# ActiveDebugger8p1.net
KiCad netlist of a schematic drawn in EAGLE
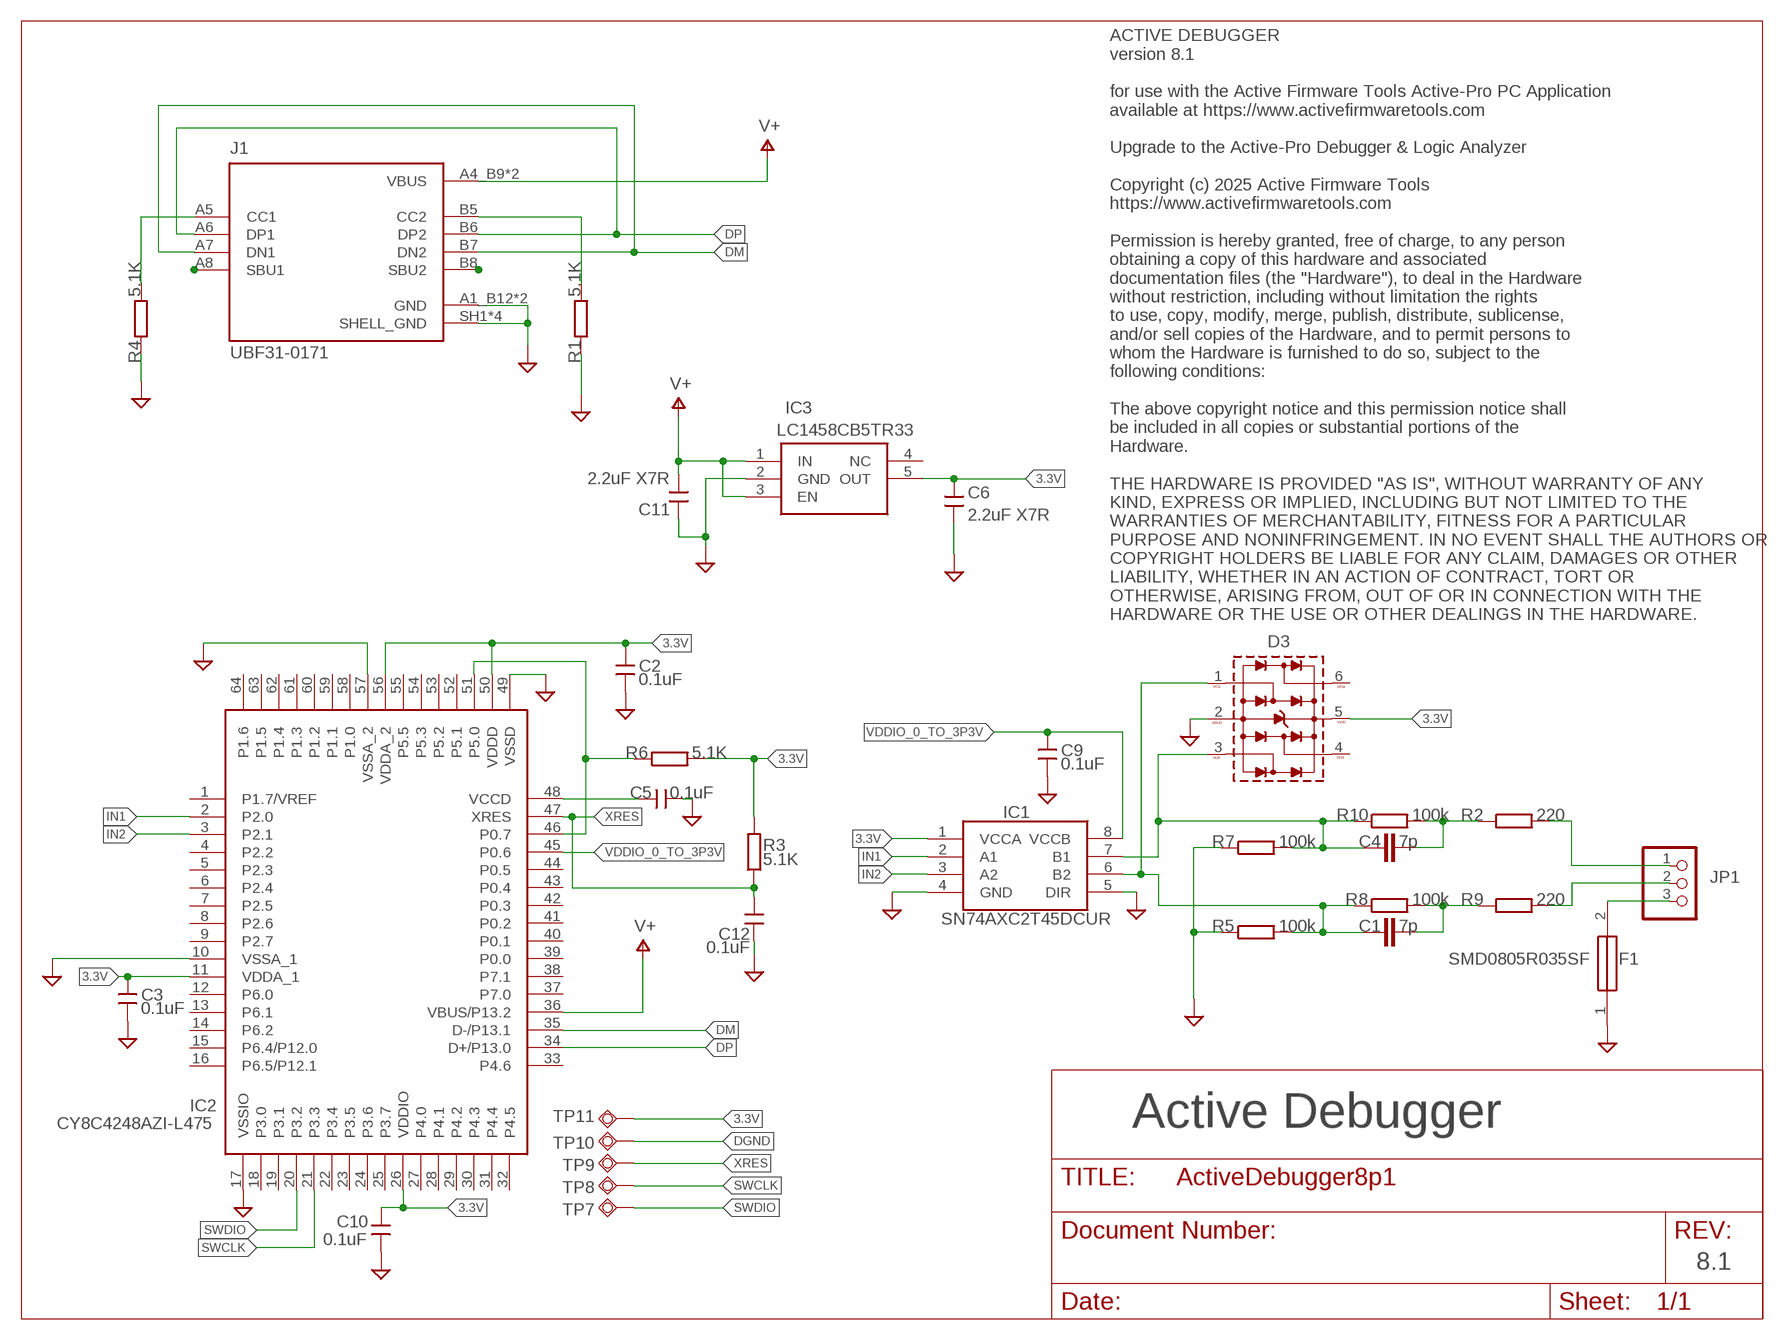
[diagram p0: schematic, sheet 1]

(export (version "E")
  (design (tool "Eeschema 10.0.6"))
  (components
    (comp (ref "C1")
      (value "7p")
      (footprint "eagle-import:C0603")
      (libsource (lib "eagle-import") (part "C-EUC0603"))
    )
    (comp (ref "C2")
      (value "0.1uF")
      (footprint "eagle-import:0603")
      (libsource (lib "eagle-import") (part "CAP0603"))
    )
    (comp (ref "C3")
      (value "0.1uF")
      (footprint "eagle-import:0603")
      (libsource (lib "eagle-import") (part "CAP0603"))
    )
    (comp (ref "C4")
      (value "7p")
      (footprint "eagle-import:C0603")
      (libsource (lib "eagle-import") (part "C-EUC0603"))
    )
    (comp (ref "C5")
      (value "0.1uF")
      (footprint "eagle-import:0603")
      (libsource (lib "eagle-import") (part "CAP0603"))
    )
    (comp (ref "C6")
      (value "2.2uF X7R")
      (footprint "eagle-import:0805")
      (libsource (lib "eagle-import") (part "CAP"))
    )
    (comp (ref "C9")
      (value "0.1uF")
      (footprint "eagle-import:0603")
      (libsource (lib "eagle-import") (part "CAP0603"))
    )
    (comp (ref "C10")
      (value "0.1uF")
      (footprint "eagle-import:0603")
      (libsource (lib "eagle-import") (part "CAP0603"))
    )
    (comp (ref "C11")
      (value "2.2uF X7R")
      (footprint "eagle-import:0805")
      (libsource (lib "eagle-import") (part "CAP"))
    )
    (comp (ref "C12")
      (value "0.1uF")
      (footprint "eagle-import:0603")
      (libsource (lib "eagle-import") (part "CAP0603"))
    )
    (comp (ref "D3")
      (value "5Vdc")
      (footprint "eagle-import:WE-TVS_SC70-6L")
      (libsource (lib "eagle-import") (part "WE-TVS-HS_SC70-6L_82400274"))
    )
    (comp (ref "F1")
      (value "SMD0805R035SF")
      (footprint "eagle-import:FUSC2114X100N")
      (fields
        (field (name "MANUFACTURER_PART_NUMBER") "SMD0805B010TF")
        (field (name "MOUSER_PART_NUMBER") "603-SMD0805B010TF")
      )
      (libsource (lib "eagle-import") (part "SMD0805B010TF"))
    )
    (comp (ref "IC1")
      (value "SN74AXC2T45DCUR")
      (footprint "eagle-import:SOP50P310X90-8N")
      (fields
        (field (name "MANUFACTURER_PART_NUMBER") "SN74AXCH2T45DCUR")
        (field (name "MOUSER_PART_NUMBER") "595-SN74AXCH2T45DCUR")
      )
      (libsource (lib "eagle-import") (part "SN74AXCH2T45DCUR"))
    )
    (comp (ref "IC2")
      (value "CY8C4248AZI-L475")
      (footprint "eagle-import:QFP50P1200X1200X160-64N")
      (libsource (lib "eagle-import") (part "CY8C4248AZI-L475"))
    )
    (comp (ref "IC3")
      (value "LC1458CB5TR33")
      (footprint "eagle-import:SOT95P280X145-5N")
      (fields
        (field (name "MANUFACTURER_PART_NUMBER") "TLV70233DBVR")
        (field (name "MOUSER_PART_NUMBER") "595-TLV70233DBVR")
      )
      (libsource (lib "eagle-import") (part "TLV70233DBVR"))
    )
    (comp (ref "J1")
      (value "UBF31-0171")
      (footprint "eagle-import:GCT_USB4105GFA120")
      (fields (field (name "MANUFACTURER") "Global Connector Technology"))
      (libsource (lib "eagle-import") (part "USB4105GFA120"))
    )
    (comp (ref "JP1")
      (value "P125-1103A0BR138A1")
      (footprint "eagle-import:1X03")
      (libsource (lib "eagle-import") (part "PINHD-1X3"))
    )
    (comp (ref "R1")
      (value "5.1K")
      (footprint "eagle-import:R0603")
      (libsource (lib "eagle-import") (part "R-EU_R0603"))
    )
    (comp (ref "R2")
      (value "220")
      (footprint "eagle-import:R0603")
      (libsource (lib "eagle-import") (part "R-EU_R0603"))
    )
    (comp (ref "R3")
      (value "5.1K")
      (footprint "eagle-import:R0603")
      (libsource (lib "eagle-import") (part "R-EU_R0603"))
    )
    (comp (ref "R4")
      (value "5.1K")
      (footprint "eagle-import:R0603")
      (libsource (lib "eagle-import") (part "R-EU_R0603"))
    )
    (comp (ref "R5")
      (value "100k")
      (footprint "eagle-import:R0603")
      (libsource (lib "eagle-import") (part "R-EU_R0603"))
    )
    (comp (ref "R6")
      (value "5.1K")
      (footprint "eagle-import:R0603")
      (libsource (lib "eagle-import") (part "R-EU_R0603"))
    )
    (comp (ref "R7")
      (value "100k")
      (footprint "eagle-import:R0603")
      (libsource (lib "eagle-import") (part "R-EU_R0603"))
    )
    (comp (ref "R8")
      (value "100k")
      (footprint "eagle-import:R0603")
      (libsource (lib "eagle-import") (part "R-EU_R0603"))
    )
    (comp (ref "R9")
      (value "220")
      (footprint "eagle-import:R0603")
      (libsource (lib "eagle-import") (part "R-EU_R0603"))
    )
    (comp (ref "R10")
      (value "100k")
      (footprint "eagle-import:R0603")
      (libsource (lib "eagle-import") (part "R-EU_R0603"))
    )
    (comp (ref "TP7")
      (value "TPSQTP20R")
      (footprint "eagle-import:TP20R")
      (libsource (lib "eagle-import") (part "TPSQTP20R"))
    )
    (comp (ref "TP8")
      (value "TPSQTP20R")
      (footprint "eagle-import:TP20R")
      (libsource (lib "eagle-import") (part "TPSQTP20R"))
    )
    (comp (ref "TP9")
      (value "TPSQTP20R")
      (footprint "eagle-import:TP20R")
      (libsource (lib "eagle-import") (part "TPSQTP20R"))
    )
    (comp (ref "TP10")
      (value "TPSQTP20R")
      (footprint "eagle-import:TP20R")
      (libsource (lib "eagle-import") (part "TPSQTP20R"))
    )
    (comp (ref "TP11")
      (value "TPSQTP20SQ")
      (footprint "eagle-import:TP20SQ")
      (libsource (lib "eagle-import") (part "TPSQTP20SQ"))
    )
  )
  (nets
    (net (code "1") (name "3.3V") (class "Default")
      (node (ref "C10") (pin "1") (pinfunction "X_1") (pintype "passive"))
      (node (ref "C2") (pin "1") (pinfunction "X_1") (pintype "passive"))
      (node (ref "C3") (pin "1") (pinfunction "X_1") (pintype "passive"))
      (node (ref "C6") (pin "2") (pinfunction "Y_2") (pintype "passive"))
      (node (ref "D3") (pin "5") (pinfunction "VDD_5") (pintype "passive"))
      (node (ref "IC1") (pin "1") (pinfunction "VCCA_1") (pintype "bidirectional"))
      (node (ref "IC2") (pin "11") (pinfunction "VDDA_1_11") (pintype "bidirectional"))
      (node (ref "IC2") (pin "26") (pinfunction "VDDIO_26") (pintype "bidirectional"))
      (node (ref "IC2") (pin "50") (pinfunction "VDDD_50") (pintype "bidirectional"))
      (node (ref "IC2") (pin "56") (pinfunction "VDDA_2_56") (pintype "bidirectional"))
      (node (ref "IC3") (pin "5") (pinfunction "OUT_5") (pintype "bidirectional"))
      (node (ref "R3") (pin "2") (pinfunction "2_2") (pintype "passive"))
      (node (ref "R6") (pin "2") (pinfunction "2_2") (pintype "passive"))
      (node (ref "TP11") (pin "TP") (pinfunction "TP_TP") (pintype "input"))
    )
    (net (code "2") (name "DGND") (class "Default")
      (node (ref "C10") (pin "2") (pinfunction "Y_2") (pintype "passive"))
      (node (ref "C11") (pin "1") (pinfunction "X_1") (pintype "passive"))
      (node (ref "C12") (pin "1") (pinfunction "X_1") (pintype "passive"))
      (node (ref "C2") (pin "2") (pinfunction "Y_2") (pintype "passive"))
      (node (ref "C3") (pin "2") (pinfunction "Y_2") (pintype "passive"))
      (node (ref "C5") (pin "2") (pinfunction "Y_2") (pintype "passive"))
      (node (ref "C6") (pin "1") (pinfunction "X_1") (pintype "passive"))
      (node (ref "C9") (pin "2") (pinfunction "Y_2") (pintype "passive"))
      (node (ref "D3") (pin "2") (pinfunction "GND_2") (pintype "passive"))
      (node (ref "F1") (pin "1") (pinfunction "1_1") (pintype "bidirectional"))
      (node (ref "IC1") (pin "4") (pinfunction "GND_4") (pintype "bidirectional"))
      (node (ref "IC1") (pin "5") (pinfunction "DIR_5") (pintype "bidirectional"))
      (node (ref "IC2") (pin "10") (pinfunction "VSSA_1_10") (pintype "bidirectional"))
      (node (ref "IC2") (pin "17") (pinfunction "VSSIO_17") (pintype "bidirectional"))
      (node (ref "IC2") (pin "49") (pinfunction "VSSD_49") (pintype "bidirectional"))
      (node (ref "IC2") (pin "57") (pinfunction "VSSA_2_57") (pintype "bidirectional"))
      (node (ref "IC3") (pin "2") (pinfunction "GND_2") (pintype "bidirectional"))
      (node (ref "J1") (pin "A1_B12") (pinfunction "GND_A1_B12") (pintype "power_in"))
      (node (ref "J1") (pin "B1_A12") (pinfunction "GND_B1_A12") (pintype "power_in"))
      (node (ref "J1") (pin "SH1") (pinfunction "SHELL_GND_SH1") (pintype "power_in"))
      (node (ref "J1") (pin "SH2") (pinfunction "SHELL_GND_SH2") (pintype "power_in"))
      (node (ref "J1") (pin "SH3") (pinfunction "SHELL_GND_SH3") (pintype "power_in"))
      (node (ref "J1") (pin "SH4") (pinfunction "SHELL_GND_SH4") (pintype "power_in"))
      (node (ref "R1") (pin "1") (pinfunction "1_1") (pintype "passive"))
      (node (ref "R4") (pin "1") (pinfunction "1_1") (pintype "passive"))
      (node (ref "R5") (pin "1") (pinfunction "1_1") (pintype "passive"))
      (node (ref "R7") (pin "1") (pinfunction "1_1") (pintype "passive"))
      (node (ref "TP10") (pin "TP") (pinfunction "TP_TP") (pintype "input"))
    )
    (net (code "3") (name "DM") (class "Default")
      (node (ref "IC2") (pin "35") (pinfunction "D-/P13.1_35") (pintype "bidirectional"))
      (node (ref "J1") (pin "A7") (pinfunction "DN1_A7") (pintype "bidirectional"))
      (node (ref "J1") (pin "B7") (pinfunction "DN2_B7") (pintype "bidirectional"))
    )
    (net (code "4") (name "DP") (class "Default")
      (node (ref "IC2") (pin "34") (pinfunction "D+/P13.0_34") (pintype "bidirectional"))
      (node (ref "J1") (pin "A6") (pinfunction "DP1_A6") (pintype "bidirectional"))
      (node (ref "J1") (pin "B6") (pinfunction "DP2_B6") (pintype "bidirectional"))
    )
    (net (code "5") (name "IN1") (class "Default")
      (node (ref "IC1") (pin "2") (pinfunction "A1_2") (pintype "bidirectional"))
      (node (ref "IC2") (pin "2") (pinfunction "P2.0_2") (pintype "bidirectional"))
    )
    (net (code "6") (name "IN2") (class "Default")
      (node (ref "IC1") (pin "3") (pinfunction "A2_3") (pintype "bidirectional"))
      (node (ref "IC2") (pin "3") (pinfunction "P2.1_3") (pintype "bidirectional"))
    )
    (net (code "7") (name "Net-(C1-Pad2)") (class "Default")
      (node (ref "C1") (pin "2") (pinfunction "2_2") (pintype "passive"))
      (node (ref "R8") (pin "2") (pinfunction "2_2") (pintype "passive"))
      (node (ref "R9") (pin "1") (pinfunction "1_1") (pintype "passive"))
    )
    (net (code "8") (name "Net-(C4-Pad2)") (class "Default")
      (node (ref "C4") (pin "2") (pinfunction "2_2") (pintype "passive"))
      (node (ref "R10") (pin "2") (pinfunction "2_2") (pintype "passive"))
      (node (ref "R2") (pin "1") (pinfunction "1_1") (pintype "passive"))
    )
    (net (code "9") (name "Net-(C5-X)") (class "Default")
      (node (ref "C5") (pin "1") (pinfunction "X_1") (pintype "passive"))
      (node (ref "IC2") (pin "48") (pinfunction "VCCD_48") (pintype "bidirectional"))
    )
    (net (code "10") (name "Net-(F1-Pad2)") (class "Default")
      (node (ref "F1") (pin "2") (pinfunction "2_2") (pintype "bidirectional"))
      (node (ref "JP1") (pin "3") (pinfunction "3_3") (pintype "passive"))
    )
    (net (code "11") (name "Net-(IC1-B1)") (class "Default")
      (node (ref "C4") (pin "1") (pinfunction "1_1") (pintype "passive"))
      (node (ref "D3") (pin "3") (pinfunction "3_3") (pintype "passive"))
      (node (ref "IC1") (pin "7") (pinfunction "B1_7") (pintype "bidirectional"))
      (node (ref "R10") (pin "1") (pinfunction "1_1") (pintype "passive"))
      (node (ref "R7") (pin "2") (pinfunction "2_2") (pintype "passive"))
    )
    (net (code "12") (name "Net-(IC1-B2)") (class "Default")
      (node (ref "C1") (pin "1") (pinfunction "1_1") (pintype "passive"))
      (node (ref "D3") (pin "1") (pinfunction "1_1") (pintype "passive"))
      (node (ref "IC1") (pin "6") (pinfunction "B2_6") (pintype "bidirectional"))
      (node (ref "R5") (pin "2") (pinfunction "2_2") (pintype "passive"))
      (node (ref "R8") (pin "1") (pinfunction "1_1") (pintype "passive"))
    )
    (net (code "13") (name "Net-(IC2-P0.7)") (class "Default")
      (node (ref "IC2") (pin "46") (pinfunction "P0.7_46") (pintype "bidirectional"))
      (node (ref "IC2") (pin "51") (pinfunction "P5.0_51") (pintype "bidirectional"))
      (node (ref "R6") (pin "1") (pinfunction "1_1") (pintype "passive"))
    )
    (net (code "14") (name "Net-(J1-CC1)") (class "Default")
      (node (ref "J1") (pin "A5") (pinfunction "CC1_A5") (pintype "bidirectional"))
      (node (ref "R4") (pin "2") (pinfunction "2_2") (pintype "passive"))
    )
    (net (code "15") (name "Net-(J1-CC2)") (class "Default")
      (node (ref "J1") (pin "B5") (pinfunction "CC2_B5") (pintype "bidirectional"))
      (node (ref "R1") (pin "2") (pinfunction "2_2") (pintype "passive"))
    )
    (net (code "16") (name "Net-(JP1-Pad1)") (class "Default")
      (node (ref "JP1") (pin "1") (pinfunction "1_1") (pintype "passive"))
      (node (ref "R2") (pin "2") (pinfunction "2_2") (pintype "passive"))
    )
    (net (code "17") (name "Net-(JP1-Pad2)") (class "Default")
      (node (ref "JP1") (pin "2") (pinfunction "2_2") (pintype "passive"))
      (node (ref "R9") (pin "2") (pinfunction "2_2") (pintype "passive"))
    )
    (net (code "18") (name "SWCLK") (class "Default")
      (node (ref "IC2") (pin "21") (pinfunction "P3.3_21") (pintype "bidirectional"))
      (node (ref "TP8") (pin "TP") (pinfunction "TP_TP") (pintype "input"))
    )
    (net (code "19") (name "SWDIO") (class "Default")
      (node (ref "IC2") (pin "20") (pinfunction "P3.2_20") (pintype "bidirectional"))
      (node (ref "TP7") (pin "TP") (pinfunction "TP_TP") (pintype "input"))
    )
    (net (code "20") (name "V+") (class "Default")
      (node (ref "C11") (pin "2") (pinfunction "Y_2") (pintype "passive"))
      (node (ref "IC2") (pin "36") (pinfunction "VBUS/P13.2_36") (pintype "bidirectional"))
      (node (ref "IC3") (pin "1") (pinfunction "IN_1") (pintype "bidirectional"))
      (node (ref "IC3") (pin "3") (pinfunction "EN_3") (pintype "bidirectional"))
      (node (ref "J1") (pin "A4_B9") (pinfunction "VBUS_A4_B9") (pintype "power_in"))
      (node (ref "J1") (pin "B4_A9") (pinfunction "VBUS_B4_A9") (pintype "power_in"))
    )
    (net (code "21") (name "VDDIO_0_TO_3P3V") (class "Default")
      (node (ref "C9") (pin "1") (pinfunction "X_1") (pintype "passive"))
      (node (ref "IC1") (pin "8") (pinfunction "VCCB_8") (pintype "bidirectional"))
      (node (ref "IC2") (pin "45") (pinfunction "P0.6_45") (pintype "bidirectional"))
    )
    (net (code "22") (name "XRES") (class "Default")
      (node (ref "C12") (pin "2") (pinfunction "Y_2") (pintype "passive"))
      (node (ref "IC2") (pin "47") (pinfunction "XRES_47") (pintype "bidirectional"))
      (node (ref "R3") (pin "1") (pinfunction "1_1") (pintype "passive"))
      (node (ref "TP9") (pin "TP") (pinfunction "TP_TP") (pintype "input"))
    )
    (net (code "23") (name "unconnected-(D3-Pad4)") (class "Default")
      (node (ref "D3") (pin "4") (pinfunction "4_4") (pintype "passive"))
    )
    (net (code "24") (name "unconnected-(D3-Pad6)") (class "Default")
      (node (ref "D3") (pin "6") (pinfunction "6_6") (pintype "passive"))
    )
    (net (code "25") (name "unconnected-(IC2-P0.0-Pad39)") (class "Default")
      (node (ref "IC2") (pin "39") (pinfunction "P0.0_39") (pintype "bidirectional"))
    )
    (net (code "26") (name "unconnected-(IC2-P0.1-Pad40)") (class "Default")
      (node (ref "IC2") (pin "40") (pinfunction "P0.1_40") (pintype "bidirectional"))
    )
    (net (code "27") (name "unconnected-(IC2-P0.2-Pad41)") (class "Default")
      (node (ref "IC2") (pin "41") (pinfunction "P0.2_41") (pintype "bidirectional"))
    )
    (net (code "28") (name "unconnected-(IC2-P0.3-Pad42)") (class "Default")
      (node (ref "IC2") (pin "42") (pinfunction "P0.3_42") (pintype "bidirectional"))
    )
    (net (code "29") (name "unconnected-(IC2-P0.4-Pad43)") (class "Default")
      (node (ref "IC2") (pin "43") (pinfunction "P0.4_43") (pintype "bidirectional"))
    )
    (net (code "30") (name "unconnected-(IC2-P0.5-Pad44)") (class "Default")
      (node (ref "IC2") (pin "44") (pinfunction "P0.5_44") (pintype "bidirectional"))
    )
    (net (code "31") (name "unconnected-(IC2-P1.0-Pad58)") (class "Default")
      (node (ref "IC2") (pin "58") (pinfunction "P1.0_58") (pintype "bidirectional"))
    )
    (net (code "32") (name "unconnected-(IC2-P1.1-Pad59)") (class "Default")
      (node (ref "IC2") (pin "59") (pinfunction "P1.1_59") (pintype "bidirectional"))
    )
    (net (code "33") (name "unconnected-(IC2-P1.2-Pad60)") (class "Default")
      (node (ref "IC2") (pin "60") (pinfunction "P1.2_60") (pintype "bidirectional"))
    )
    (net (code "34") (name "unconnected-(IC2-P1.3-Pad61)") (class "Default")
      (node (ref "IC2") (pin "61") (pinfunction "P1.3_61") (pintype "bidirectional"))
    )
    (net (code "35") (name "unconnected-(IC2-P1.4-Pad62)") (class "Default")
      (node (ref "IC2") (pin "62") (pinfunction "P1.4_62") (pintype "bidirectional"))
    )
    (net (code "36") (name "unconnected-(IC2-P1.5-Pad63)") (class "Default")
      (node (ref "IC2") (pin "63") (pinfunction "P1.5_63") (pintype "bidirectional"))
    )
    (net (code "37") (name "unconnected-(IC2-P1.6-Pad64)") (class "Default")
      (node (ref "IC2") (pin "64") (pinfunction "P1.6_64") (pintype "bidirectional"))
    )
    (net (code "38") (name "unconnected-(IC2-P1.7{slash}VREF-Pad1)") (class "Default")
      (node (ref "IC2") (pin "1") (pinfunction "P1.7/VREF_1") (pintype "bidirectional"))
    )
    (net (code "39") (name "unconnected-(IC2-P2.2-Pad4)") (class "Default")
      (node (ref "IC2") (pin "4") (pinfunction "P2.2_4") (pintype "bidirectional"))
    )
    (net (code "40") (name "unconnected-(IC2-P2.3-Pad5)") (class "Default")
      (node (ref "IC2") (pin "5") (pinfunction "P2.3_5") (pintype "bidirectional"))
    )
    (net (code "41") (name "unconnected-(IC2-P2.4-Pad6)") (class "Default")
      (node (ref "IC2") (pin "6") (pinfunction "P2.4_6") (pintype "bidirectional"))
    )
    (net (code "42") (name "unconnected-(IC2-P2.5-Pad7)") (class "Default")
      (node (ref "IC2") (pin "7") (pinfunction "P2.5_7") (pintype "bidirectional"))
    )
    (net (code "43") (name "unconnected-(IC2-P2.6-Pad8)") (class "Default")
      (node (ref "IC2") (pin "8") (pinfunction "P2.6_8") (pintype "bidirectional"))
    )
    (net (code "44") (name "unconnected-(IC2-P2.7-Pad9)") (class "Default")
      (node (ref "IC2") (pin "9") (pinfunction "P2.7_9") (pintype "bidirectional"))
    )
    (net (code "45") (name "unconnected-(IC2-P3.0-Pad18)") (class "Default")
      (node (ref "IC2") (pin "18") (pinfunction "P3.0_18") (pintype "bidirectional"))
    )
    (net (code "46") (name "unconnected-(IC2-P3.1-Pad19)") (class "Default")
      (node (ref "IC2") (pin "19") (pinfunction "P3.1_19") (pintype "bidirectional"))
    )
    (net (code "47") (name "unconnected-(IC2-P3.4-Pad22)") (class "Default")
      (node (ref "IC2") (pin "22") (pinfunction "P3.4_22") (pintype "bidirectional"))
    )
    (net (code "48") (name "unconnected-(IC2-P3.5-Pad23)") (class "Default")
      (node (ref "IC2") (pin "23") (pinfunction "P3.5_23") (pintype "bidirectional"))
    )
    (net (code "49") (name "unconnected-(IC2-P3.6-Pad24)") (class "Default")
      (node (ref "IC2") (pin "24") (pinfunction "P3.6_24") (pintype "bidirectional"))
    )
    (net (code "50") (name "unconnected-(IC2-P3.7-Pad25)") (class "Default")
      (node (ref "IC2") (pin "25") (pinfunction "P3.7_25") (pintype "bidirectional"))
    )
    (net (code "51") (name "unconnected-(IC2-P4.0-Pad27)") (class "Default")
      (node (ref "IC2") (pin "27") (pinfunction "P4.0_27") (pintype "bidirectional"))
    )
    (net (code "52") (name "unconnected-(IC2-P4.1-Pad28)") (class "Default")
      (node (ref "IC2") (pin "28") (pinfunction "P4.1_28") (pintype "bidirectional"))
    )
    (net (code "53") (name "unconnected-(IC2-P4.2-Pad29)") (class "Default")
      (node (ref "IC2") (pin "29") (pinfunction "P4.2_29") (pintype "bidirectional"))
    )
    (net (code "54") (name "unconnected-(IC2-P4.3-Pad30)") (class "Default")
      (node (ref "IC2") (pin "30") (pinfunction "P4.3_30") (pintype "bidirectional"))
    )
    (net (code "55") (name "unconnected-(IC2-P4.4-Pad31)") (class "Default")
      (node (ref "IC2") (pin "31") (pinfunction "P4.4_31") (pintype "bidirectional"))
    )
    (net (code "56") (name "unconnected-(IC2-P4.5-Pad32)") (class "Default")
      (node (ref "IC2") (pin "32") (pinfunction "P4.5_32") (pintype "bidirectional"))
    )
    (net (code "57") (name "unconnected-(IC2-P4.6-Pad33)") (class "Default")
      (node (ref "IC2") (pin "33") (pinfunction "P4.6_33") (pintype "bidirectional"))
    )
    (net (code "58") (name "unconnected-(IC2-P5.1-Pad52)") (class "Default")
      (node (ref "IC2") (pin "52") (pinfunction "P5.1_52") (pintype "bidirectional"))
    )
    (net (code "59") (name "unconnected-(IC2-P5.2-Pad53)") (class "Default")
      (node (ref "IC2") (pin "53") (pinfunction "P5.2_53") (pintype "bidirectional"))
    )
    (net (code "60") (name "unconnected-(IC2-P5.3-Pad54)") (class "Default")
      (node (ref "IC2") (pin "54") (pinfunction "P5.3_54") (pintype "bidirectional"))
    )
    (net (code "61") (name "unconnected-(IC2-P5.5-Pad55)") (class "Default")
      (node (ref "IC2") (pin "55") (pinfunction "P5.5_55") (pintype "bidirectional"))
    )
    (net (code "62") (name "unconnected-(IC2-P6.0-Pad12)") (class "Default")
      (node (ref "IC2") (pin "12") (pinfunction "P6.0_12") (pintype "bidirectional"))
    )
    (net (code "63") (name "unconnected-(IC2-P6.1-Pad13)") (class "Default")
      (node (ref "IC2") (pin "13") (pinfunction "P6.1_13") (pintype "bidirectional"))
    )
    (net (code "64") (name "unconnected-(IC2-P6.2-Pad14)") (class "Default")
      (node (ref "IC2") (pin "14") (pinfunction "P6.2_14") (pintype "bidirectional"))
    )
    (net (code "65") (name "unconnected-(IC2-P6.4{slash}P12.0-Pad15)") (class "Default")
      (node (ref "IC2") (pin "15") (pinfunction "P6.4/P12.0_15") (pintype "bidirectional"))
    )
    (net (code "66") (name "unconnected-(IC2-P6.5{slash}P12.1-Pad16)") (class "Default")
      (node (ref "IC2") (pin "16") (pinfunction "P6.5/P12.1_16") (pintype "bidirectional"))
    )
    (net (code "67") (name "unconnected-(IC2-P7.0-Pad37)") (class "Default")
      (node (ref "IC2") (pin "37") (pinfunction "P7.0_37") (pintype "bidirectional"))
    )
    (net (code "68") (name "unconnected-(IC2-P7.1-Pad38)") (class "Default")
      (node (ref "IC2") (pin "38") (pinfunction "P7.1_38") (pintype "bidirectional"))
    )
    (net (code "69") (name "unconnected-(IC3-NC-Pad4)") (class "Default")
      (node (ref "IC3") (pin "4") (pinfunction "NC_4") (pintype "no_connect"))
    )
    (net (code "70") (name "unconnected-(J1-SBU1-PadA8)") (class "Default")
      (node (ref "J1") (pin "A8") (pinfunction "SBU1_A8") (pintype "bidirectional"))
    )
    (net (code "71") (name "unconnected-(J1-SBU2-PadB8)") (class "Default")
      (node (ref "J1") (pin "B8") (pinfunction "SBU2_B8") (pintype "bidirectional"))
    )
  )
)
